# antenna.net
KiCad netlist of a schematic drawn in EAGLE
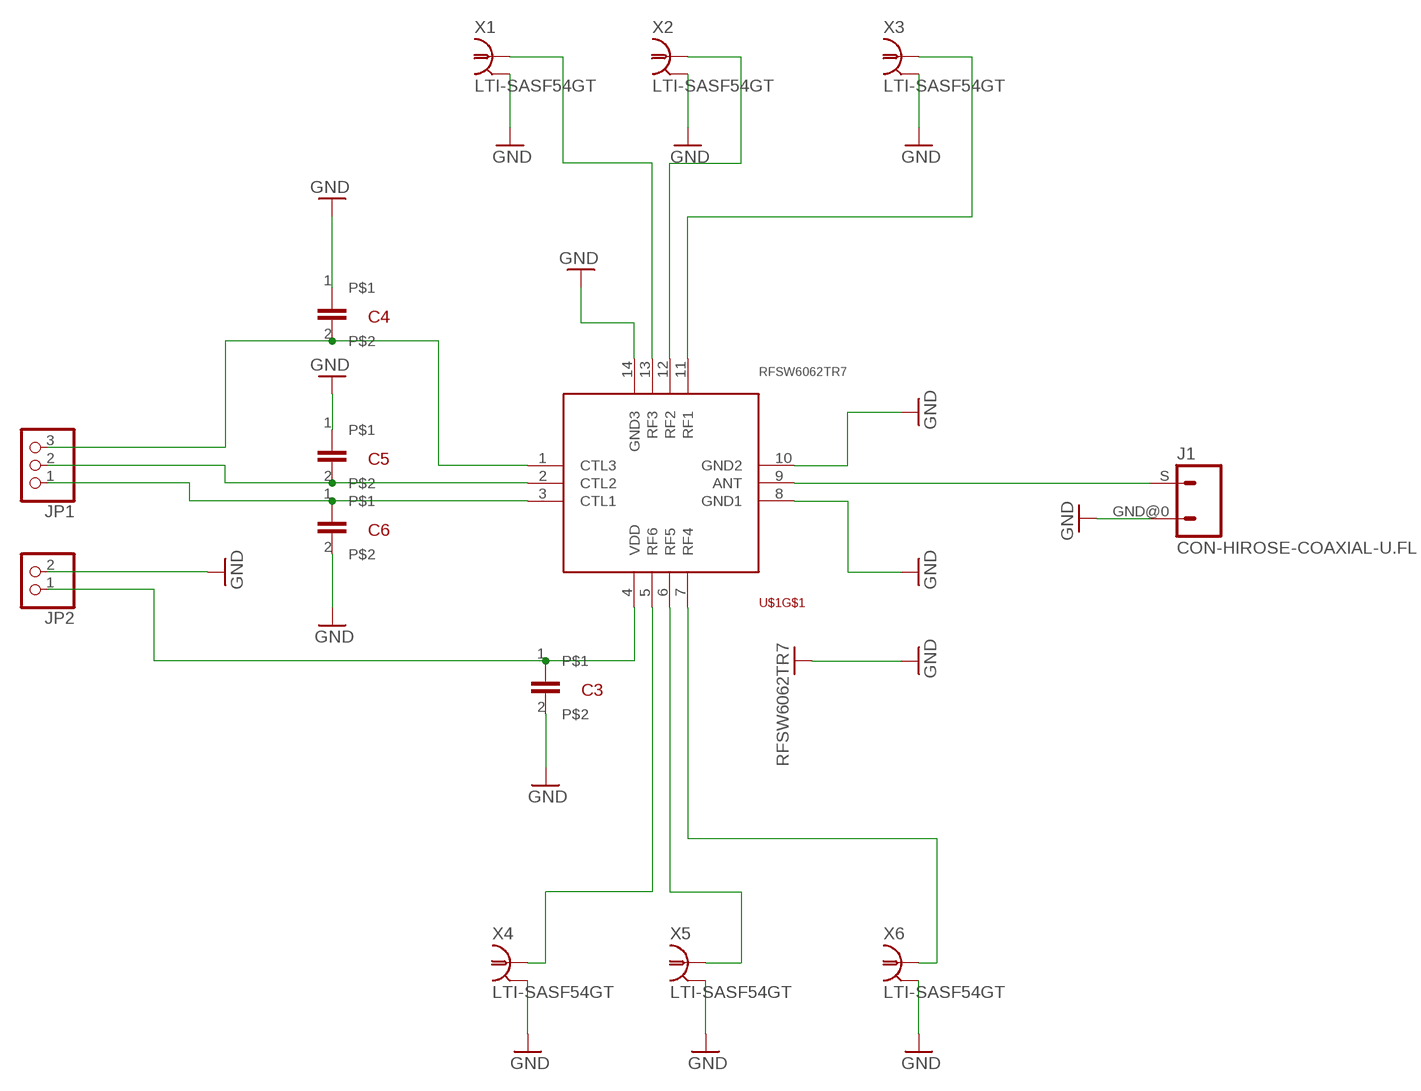
[diagram p0: schematic, sheet 1]

(export (version "E")
  (design (tool "Eeschema 10.0.6"))
  (components
    (comp (ref "C3")
      (value "C3_0.01µF")
      (footprint "eagle-import:CAPC2012X78N")
      (libsource (lib "eagle-import") (part "C3_0.01µF"))
    )
    (comp (ref "C4")
      (value "C8_100PF")
      (footprint "eagle-import:CAPC2012X78N")
      (libsource (lib "eagle-import") (part "C8_100PF"))
    )
    (comp (ref "C5")
      (value "C8_100PF")
      (footprint "eagle-import:CAPC2012X78N")
      (libsource (lib "eagle-import") (part "C8_100PF"))
    )
    (comp (ref "C6")
      (value "C8_100PF")
      (footprint "eagle-import:CAPC2012X78N")
      (libsource (lib "eagle-import") (part "C8_100PF"))
    )
    (comp (ref "J1")
      (value "CON-HIROSE-COAXIAL-U.FL")
      (footprint "eagle-import:CON-U.FL")
      (libsource (lib "eagle-import") (part "CON-HIROSE-COAXIAL-U.FL"))
    )
    (comp (ref "JP1")
      (value "PINHD-1X3")
      (footprint "eagle-import:1X03")
      (libsource (lib "eagle-import") (part "PINHD-1X3"))
    )
    (comp (ref "JP2")
      (value "PINHD-1X2")
      (footprint "eagle-import:1X02")
      (libsource (lib "eagle-import") (part "PINHD-1X2"))
    )
    (comp (ref "U$1")
      (value "RFSW6062TR7")
      (footprint "eagle-import:QFN40P200X200X55-15T98N")
      (libsource (lib "eagle-import") (part "RFSW6062TR7"))
    )
    (comp (ref "X1")
      (value "LTI-SASF54GT")
      (footprint "eagle-import:LTI-SASF54GT")
      (libsource (lib "eagle-import") (part "LTI-SASF54GT"))
    )
    (comp (ref "X2")
      (value "LTI-SASF54GT")
      (footprint "eagle-import:LTI-SASF54GT")
      (libsource (lib "eagle-import") (part "LTI-SASF54GT"))
    )
    (comp (ref "X3")
      (value "LTI-SASF54GT")
      (footprint "eagle-import:LTI-SASF54GT")
      (libsource (lib "eagle-import") (part "LTI-SASF54GT"))
    )
    (comp (ref "X4")
      (value "LTI-SASF54GT")
      (footprint "eagle-import:LTI-SASF54GT")
      (libsource (lib "eagle-import") (part "LTI-SASF54GT"))
    )
    (comp (ref "X5")
      (value "LTI-SASF54GT")
      (footprint "eagle-import:LTI-SASF54GT")
      (libsource (lib "eagle-import") (part "LTI-SASF54GT"))
    )
    (comp (ref "X6")
      (value "LTI-SASF54GT")
      (footprint "eagle-import:LTI-SASF54GT")
      (libsource (lib "eagle-import") (part "LTI-SASF54GT"))
    )
  )
  (nets
    (net (code "1") (name "GND") (class "Default")
      (node (ref "C3") (pin "2") (pinfunction "P$2_2") (pintype "bidirectional"))
      (node (ref "C4") (pin "1") (pinfunction "P$1_1") (pintype "bidirectional"))
      (node (ref "C5") (pin "1") (pinfunction "P$1_1") (pintype "bidirectional"))
      (node (ref "C6") (pin "2") (pinfunction "P$2_2") (pintype "bidirectional"))
      (node (ref "J1") (pin "GND@0") (pinfunction "2_GND@0") (pintype "passive"))
      (node (ref "JP2") (pin "2") (pinfunction "2_2") (pintype "passive"))
      (node (ref "U$1") (pin "10") (pinfunction "GND2_10") (pintype "bidirectional"))
      (node (ref "U$1") (pin "14") (pinfunction "GND3_14") (pintype "bidirectional"))
      (node (ref "U$1") (pin "15") (pinfunction "GND_15") (pintype "power_in"))
      (node (ref "U$1") (pin "8") (pinfunction "GND1_8") (pintype "bidirectional"))
      (node (ref "X1") (pin "2") (pinfunction "2_2") (pintype "passive"))
      (node (ref "X1") (pin "3") (pinfunction "2_3") (pintype "passive"))
      (node (ref "X1") (pin "4") (pinfunction "2_4") (pintype "passive"))
      (node (ref "X1") (pin "5") (pinfunction "2_5") (pintype "passive"))
      (node (ref "X2") (pin "2") (pinfunction "2_2") (pintype "passive"))
      (node (ref "X2") (pin "3") (pinfunction "2_3") (pintype "passive"))
      (node (ref "X2") (pin "4") (pinfunction "2_4") (pintype "passive"))
      (node (ref "X2") (pin "5") (pinfunction "2_5") (pintype "passive"))
      (node (ref "X3") (pin "2") (pinfunction "2_2") (pintype "passive"))
      (node (ref "X3") (pin "3") (pinfunction "2_3") (pintype "passive"))
      (node (ref "X3") (pin "4") (pinfunction "2_4") (pintype "passive"))
      (node (ref "X3") (pin "5") (pinfunction "2_5") (pintype "passive"))
      (node (ref "X4") (pin "2") (pinfunction "2_2") (pintype "passive"))
      (node (ref "X4") (pin "3") (pinfunction "2_3") (pintype "passive"))
      (node (ref "X4") (pin "4") (pinfunction "2_4") (pintype "passive"))
      (node (ref "X4") (pin "5") (pinfunction "2_5") (pintype "passive"))
      (node (ref "X5") (pin "2") (pinfunction "2_2") (pintype "passive"))
      (node (ref "X5") (pin "3") (pinfunction "2_3") (pintype "passive"))
      (node (ref "X5") (pin "4") (pinfunction "2_4") (pintype "passive"))
      (node (ref "X5") (pin "5") (pinfunction "2_5") (pintype "passive"))
      (node (ref "X6") (pin "2") (pinfunction "2_2") (pintype "passive"))
      (node (ref "X6") (pin "3") (pinfunction "2_3") (pintype "passive"))
      (node (ref "X6") (pin "4") (pinfunction "2_4") (pintype "passive"))
      (node (ref "X6") (pin "5") (pinfunction "2_5") (pintype "passive"))
    )
    (net (code "2") (name "Net-(C3-P$1)") (class "Default")
      (node (ref "C3") (pin "1") (pinfunction "P$1_1") (pintype "bidirectional"))
      (node (ref "JP2") (pin "1") (pinfunction "1_1") (pintype "passive"))
      (node (ref "U$1") (pin "4") (pinfunction "VDD_4") (pintype "bidirectional"))
    )
    (net (code "3") (name "Net-(C4-P$2)") (class "Default")
      (node (ref "C4") (pin "2") (pinfunction "P$2_2") (pintype "bidirectional"))
      (node (ref "JP1") (pin "3") (pinfunction "3_3") (pintype "passive"))
      (node (ref "U$1") (pin "1") (pinfunction "CTL3_1") (pintype "bidirectional"))
    )
    (net (code "4") (name "Net-(C5-P$2)") (class "Default")
      (node (ref "C5") (pin "2") (pinfunction "P$2_2") (pintype "bidirectional"))
      (node (ref "JP1") (pin "2") (pinfunction "2_2") (pintype "passive"))
      (node (ref "U$1") (pin "2") (pinfunction "CTL2_2") (pintype "bidirectional"))
    )
    (net (code "5") (name "Net-(C6-P$1)") (class "Default")
      (node (ref "C6") (pin "1") (pinfunction "P$1_1") (pintype "bidirectional"))
      (node (ref "JP1") (pin "1") (pinfunction "1_1") (pintype "passive"))
      (node (ref "U$1") (pin "3") (pinfunction "CTL1_3") (pintype "bidirectional"))
    )
    (net (code "6") (name "Net-(J1-1)") (class "Default")
      (node (ref "J1") (pin "S") (pinfunction "1_S") (pintype "passive"))
      (node (ref "U$1") (pin "9") (pinfunction "ANT_9") (pintype "bidirectional"))
    )
    (net (code "7") (name "Net-(U$1A-RF1)") (class "Default")
      (node (ref "U$1") (pin "11") (pinfunction "RF1_11") (pintype "bidirectional"))
      (node (ref "X3") (pin "1") (pinfunction "1_1") (pintype "passive"))
    )
    (net (code "8") (name "Net-(U$1A-RF2)") (class "Default")
      (node (ref "U$1") (pin "12") (pinfunction "RF2_12") (pintype "bidirectional"))
      (node (ref "X2") (pin "1") (pinfunction "1_1") (pintype "passive"))
    )
    (net (code "9") (name "Net-(U$1A-RF3)") (class "Default")
      (node (ref "U$1") (pin "13") (pinfunction "RF3_13") (pintype "bidirectional"))
      (node (ref "X1") (pin "1") (pinfunction "1_1") (pintype "passive"))
    )
    (net (code "10") (name "Net-(U$1A-RF4)") (class "Default")
      (node (ref "U$1") (pin "7") (pinfunction "RF4_7") (pintype "bidirectional"))
      (node (ref "X6") (pin "1") (pinfunction "1_1") (pintype "passive"))
    )
    (net (code "11") (name "Net-(U$1A-RF5)") (class "Default")
      (node (ref "U$1") (pin "6") (pinfunction "RF5_6") (pintype "bidirectional"))
      (node (ref "X5") (pin "1") (pinfunction "1_1") (pintype "passive"))
    )
    (net (code "12") (name "Net-(U$1A-RF6)") (class "Default")
      (node (ref "U$1") (pin "5") (pinfunction "RF6_5") (pintype "bidirectional"))
      (node (ref "X4") (pin "1") (pinfunction "1_1") (pintype "passive"))
    )
  )
)
